# Rs485hub.net
KiCad netlist of a schematic drawn in EAGLE
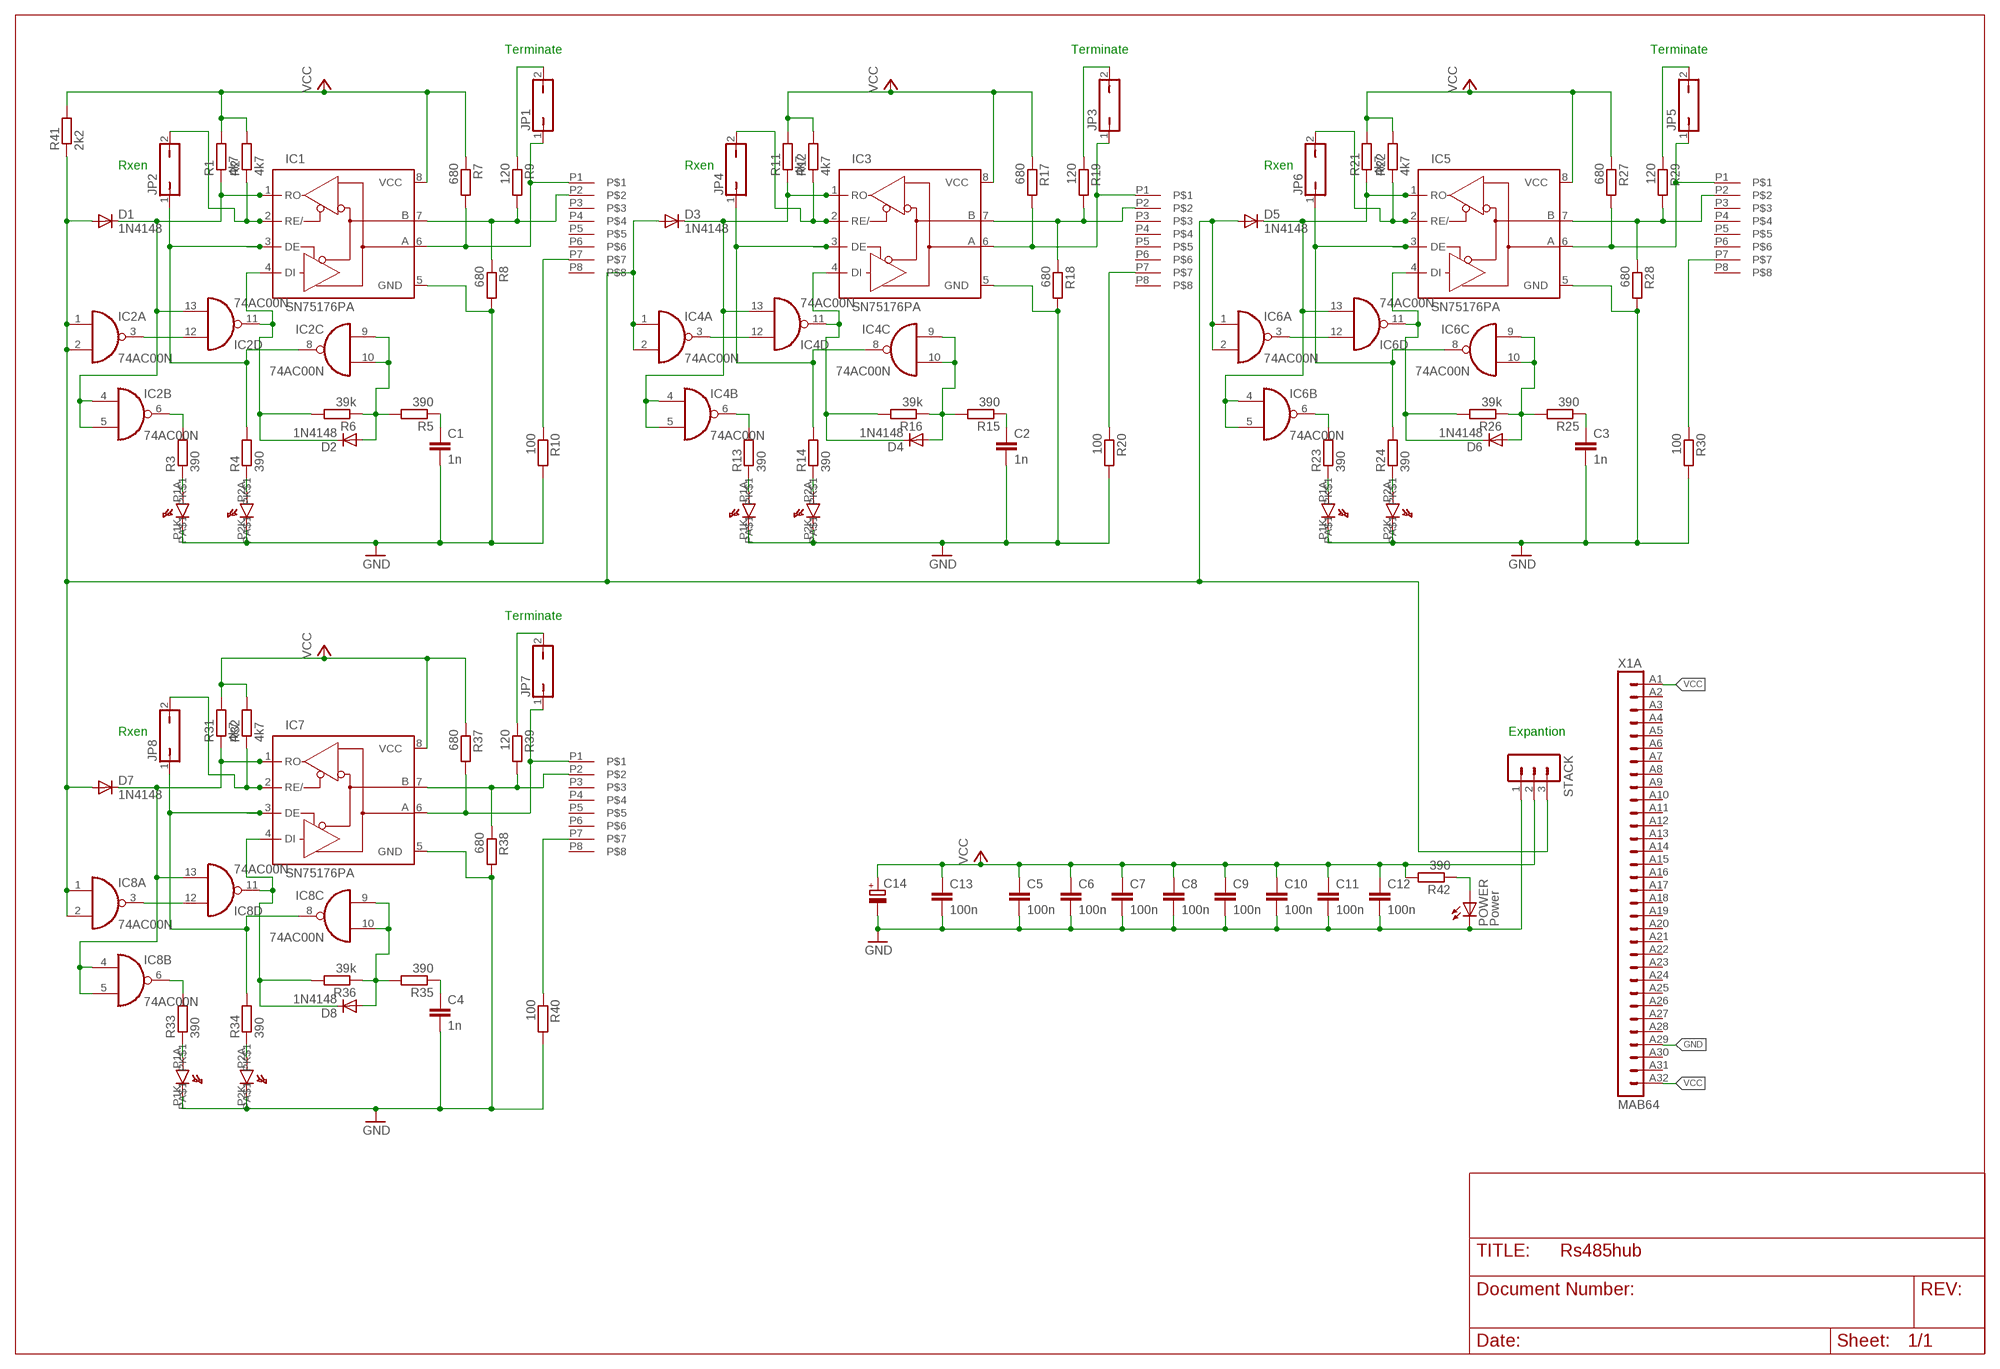
[diagram p0: schematic, sheet 1]

(export (version "E")
  (design (tool "Eeschema 10.0.6"))
  (components
    (comp (ref "C1")
      (value "1n")
      (footprint "eagle-import:C2.5-3")
      (libsource (lib "eagle-import") (part "C2,5-3"))
    )
    (comp (ref "C2")
      (value "1n")
      (footprint "eagle-import:C2.5-3")
      (libsource (lib "eagle-import") (part "C2,5-3"))
    )
    (comp (ref "C3")
      (value "1n")
      (footprint "eagle-import:C2.5-3")
      (libsource (lib "eagle-import") (part "C2,5-3"))
    )
    (comp (ref "C4")
      (value "1n")
      (footprint "eagle-import:C2.5-3")
      (libsource (lib "eagle-import") (part "C2,5-3"))
    )
    (comp (ref "C5")
      (value "100n")
      (footprint "eagle-import:C2.5-3")
      (libsource (lib "eagle-import") (part "C2,5-3"))
    )
    (comp (ref "C6")
      (value "100n")
      (footprint "eagle-import:C2.5-3")
      (libsource (lib "eagle-import") (part "C2,5-3"))
    )
    (comp (ref "C7")
      (value "100n")
      (footprint "eagle-import:C2.5-3")
      (libsource (lib "eagle-import") (part "C2,5-3"))
    )
    (comp (ref "C8")
      (value "100n")
      (footprint "eagle-import:C2.5-3")
      (libsource (lib "eagle-import") (part "C2,5-3"))
    )
    (comp (ref "C9")
      (value "100n")
      (footprint "eagle-import:C2.5-3")
      (libsource (lib "eagle-import") (part "C2,5-3"))
    )
    (comp (ref "C10")
      (value "100n")
      (footprint "eagle-import:C2.5-3")
      (libsource (lib "eagle-import") (part "C2,5-3"))
    )
    (comp (ref "C11")
      (value "100n")
      (footprint "eagle-import:C2.5-3")
      (libsource (lib "eagle-import") (part "C2,5-3"))
    )
    (comp (ref "C12")
      (value "100n")
      (footprint "eagle-import:C2.5-3")
      (libsource (lib "eagle-import") (part "C2,5-3"))
    )
    (comp (ref "C13")
      (value "100n")
      (footprint "eagle-import:C2.5-3")
      (libsource (lib "eagle-import") (part "C2,5-3"))
    )
    (comp (ref "C14")
      (value "CPOL-EUE5-8.5")
      (footprint "eagle-import:E5-8,5")
      (libsource (lib "eagle-import") (part "CPOL-EUE5-8.5"))
    )
    (comp (ref "D1")
      (value "1N4148")
      (footprint "eagle-import:DO35-10")
      (libsource (lib "eagle-import") (part "1N4148"))
    )
    (comp (ref "D2")
      (value "1N4148")
      (footprint "eagle-import:DO35-10")
      (libsource (lib "eagle-import") (part "1N4148"))
    )
    (comp (ref "D3")
      (value "1N4148")
      (footprint "eagle-import:DO35-10")
      (libsource (lib "eagle-import") (part "1N4148"))
    )
    (comp (ref "D4")
      (value "1N4148")
      (footprint "eagle-import:DO35-10")
      (libsource (lib "eagle-import") (part "1N4148"))
    )
    (comp (ref "D5")
      (value "1N4148")
      (footprint "eagle-import:DO35-10")
      (libsource (lib "eagle-import") (part "1N4148"))
    )
    (comp (ref "D6")
      (value "1N4148")
      (footprint "eagle-import:DO35-10")
      (libsource (lib "eagle-import") (part "1N4148"))
    )
    (comp (ref "D7")
      (value "1N4148")
      (footprint "eagle-import:DO35-10")
      (libsource (lib "eagle-import") (part "1N4148"))
    )
    (comp (ref "D8")
      (value "1N4148")
      (footprint "eagle-import:DO35-10")
      (libsource (lib "eagle-import") (part "1N4148"))
    )
    (comp (ref "IC1")
      (value "SN75176PA")
      (footprint "eagle-import:DIL08")
      (libsource (lib "eagle-import") (part "SN75176PA"))
    )
    (comp (ref "IC2")
      (value "74AC00N")
      (footprint "eagle-import:DIL14")
      (libsource (lib "eagle-import") (part "7400NAC"))
    )
    (comp (ref "IC3")
      (value "SN75176PA")
      (footprint "eagle-import:DIL08")
      (libsource (lib "eagle-import") (part "SN75176PA"))
    )
    (comp (ref "IC4")
      (value "74AC00N")
      (footprint "eagle-import:DIL14")
      (libsource (lib "eagle-import") (part "7400NAC"))
    )
    (comp (ref "IC5")
      (value "SN75176PA")
      (footprint "eagle-import:DIL08")
      (libsource (lib "eagle-import") (part "SN75176PA"))
    )
    (comp (ref "IC6")
      (value "74AC00N")
      (footprint "eagle-import:DIL14")
      (libsource (lib "eagle-import") (part "7400NAC"))
    )
    (comp (ref "IC7")
      (value "SN75176PA")
      (footprint "eagle-import:DIL08")
      (libsource (lib "eagle-import") (part "SN75176PA"))
    )
    (comp (ref "IC8")
      (value "74AC00N")
      (footprint "eagle-import:DIL14")
      (libsource (lib "eagle-import") (part "7400NAC"))
    )
    (comp (ref "JP1")
      (value "JP1Q")
      (footprint "eagle-import:JP1")
      (libsource (lib "eagle-import") (part "JP1Q"))
    )
    (comp (ref "JP2")
      (value "JP1Q")
      (footprint "eagle-import:JP1")
      (libsource (lib "eagle-import") (part "JP1Q"))
    )
    (comp (ref "JP3")
      (value "JP1Q")
      (footprint "eagle-import:JP1")
      (libsource (lib "eagle-import") (part "JP1Q"))
    )
    (comp (ref "JP4")
      (value "JP1Q")
      (footprint "eagle-import:JP1")
      (libsource (lib "eagle-import") (part "JP1Q"))
    )
    (comp (ref "JP5")
      (value "JP1Q")
      (footprint "eagle-import:JP1")
      (libsource (lib "eagle-import") (part "JP1Q"))
    )
    (comp (ref "JP6")
      (value "JP1Q")
      (footprint "eagle-import:JP1")
      (libsource (lib "eagle-import") (part "JP1Q"))
    )
    (comp (ref "JP7")
      (value "JP1Q")
      (footprint "eagle-import:JP1")
      (libsource (lib "eagle-import") (part "JP1Q"))
    )
    (comp (ref "JP8")
      (value "JP1Q")
      (footprint "eagle-import:JP1")
      (libsource (lib "eagle-import") (part "JP1Q"))
    )
    (comp (ref "POWER")
      (value "Power")
      (footprint "eagle-import:LED3MM")
      (libsource (lib "eagle-import") (part "LED3MM"))
    )
    (comp (ref "R1")
      (value "4k7")
      (footprint "eagle-import:0309_10")
      (libsource (lib "eagle-import") (part "R-EU_0309/10"))
    )
    (comp (ref "R2")
      (value "4k7")
      (footprint "eagle-import:0309_10")
      (libsource (lib "eagle-import") (part "R-EU_0309/10"))
    )
    (comp (ref "R3")
      (value "390")
      (footprint "eagle-import:0309_10")
      (libsource (lib "eagle-import") (part "R-EU_0309/10"))
    )
    (comp (ref "R4")
      (value "390")
      (footprint "eagle-import:0309_10")
      (libsource (lib "eagle-import") (part "R-EU_0309/10"))
    )
    (comp (ref "R5")
      (value "390")
      (footprint "eagle-import:0309_10")
      (libsource (lib "eagle-import") (part "R-EU_0309/10"))
    )
    (comp (ref "R6")
      (value "39k")
      (footprint "eagle-import:0309_10")
      (libsource (lib "eagle-import") (part "R-EU_0309/10"))
    )
    (comp (ref "R7")
      (value "680")
      (footprint "eagle-import:0309_10")
      (libsource (lib "eagle-import") (part "R-EU_0309/10"))
    )
    (comp (ref "R8")
      (value "680")
      (footprint "eagle-import:0309_10")
      (libsource (lib "eagle-import") (part "R-EU_0309/10"))
    )
    (comp (ref "R9")
      (value "120")
      (footprint "eagle-import:0309_10")
      (libsource (lib "eagle-import") (part "R-EU_0309/10"))
    )
    (comp (ref "R10")
      (value "100")
      (footprint "eagle-import:0309_10")
      (libsource (lib "eagle-import") (part "R-EU_0309/10"))
    )
    (comp (ref "R11")
      (value "4k7")
      (footprint "eagle-import:0309_10")
      (libsource (lib "eagle-import") (part "R-EU_0309/10"))
    )
    (comp (ref "R12")
      (value "4k7")
      (footprint "eagle-import:0309_10")
      (libsource (lib "eagle-import") (part "R-EU_0309/10"))
    )
    (comp (ref "R13")
      (value "390")
      (footprint "eagle-import:0309_10")
      (libsource (lib "eagle-import") (part "R-EU_0309/10"))
    )
    (comp (ref "R14")
      (value "390")
      (footprint "eagle-import:0309_10")
      (libsource (lib "eagle-import") (part "R-EU_0309/10"))
    )
    (comp (ref "R15")
      (value "390")
      (footprint "eagle-import:0309_10")
      (libsource (lib "eagle-import") (part "R-EU_0309/10"))
    )
    (comp (ref "R16")
      (value "39k")
      (footprint "eagle-import:0309_10")
      (libsource (lib "eagle-import") (part "R-EU_0309/10"))
    )
    (comp (ref "R17")
      (value "680")
      (footprint "eagle-import:0309_10")
      (libsource (lib "eagle-import") (part "R-EU_0309/10"))
    )
    (comp (ref "R18")
      (value "680")
      (footprint "eagle-import:0309_10")
      (libsource (lib "eagle-import") (part "R-EU_0309/10"))
    )
    (comp (ref "R19")
      (value "120")
      (footprint "eagle-import:0309_10")
      (libsource (lib "eagle-import") (part "R-EU_0309/10"))
    )
    (comp (ref "R20")
      (value "100")
      (footprint "eagle-import:0309_10")
      (libsource (lib "eagle-import") (part "R-EU_0309/10"))
    )
    (comp (ref "R21")
      (value "4k7")
      (footprint "eagle-import:0309_10")
      (libsource (lib "eagle-import") (part "R-EU_0309/10"))
    )
    (comp (ref "R22")
      (value "4k7")
      (footprint "eagle-import:0309_10")
      (libsource (lib "eagle-import") (part "R-EU_0309/10"))
    )
    (comp (ref "R23")
      (value "390")
      (footprint "eagle-import:0309_10")
      (libsource (lib "eagle-import") (part "R-EU_0309/10"))
    )
    (comp (ref "R24")
      (value "390")
      (footprint "eagle-import:0309_10")
      (libsource (lib "eagle-import") (part "R-EU_0309/10"))
    )
    (comp (ref "R25")
      (value "390")
      (footprint "eagle-import:0309_10")
      (libsource (lib "eagle-import") (part "R-EU_0309/10"))
    )
    (comp (ref "R26")
      (value "39k")
      (footprint "eagle-import:0309_10")
      (libsource (lib "eagle-import") (part "R-EU_0309/10"))
    )
    (comp (ref "R27")
      (value "680")
      (footprint "eagle-import:0309_10")
      (libsource (lib "eagle-import") (part "R-EU_0309/10"))
    )
    (comp (ref "R28")
      (value "680")
      (footprint "eagle-import:0309_10")
      (libsource (lib "eagle-import") (part "R-EU_0309/10"))
    )
    (comp (ref "R29")
      (value "120")
      (footprint "eagle-import:0309_10")
      (libsource (lib "eagle-import") (part "R-EU_0309/10"))
    )
    (comp (ref "R30")
      (value "100")
      (footprint "eagle-import:0309_10")
      (libsource (lib "eagle-import") (part "R-EU_0309/10"))
    )
    (comp (ref "R31")
      (value "4k7")
      (footprint "eagle-import:0309_10")
      (libsource (lib "eagle-import") (part "R-EU_0309/10"))
    )
    (comp (ref "R32")
      (value "4k7")
      (footprint "eagle-import:0309_10")
      (libsource (lib "eagle-import") (part "R-EU_0309/10"))
    )
    (comp (ref "R33")
      (value "390")
      (footprint "eagle-import:0309_10")
      (libsource (lib "eagle-import") (part "R-EU_0309/10"))
    )
    (comp (ref "R34")
      (value "390")
      (footprint "eagle-import:0309_10")
      (libsource (lib "eagle-import") (part "R-EU_0309/10"))
    )
    (comp (ref "R35")
      (value "390")
      (footprint "eagle-import:0309_10")
      (libsource (lib "eagle-import") (part "R-EU_0309/10"))
    )
    (comp (ref "R36")
      (value "39k")
      (footprint "eagle-import:0309_10")
      (libsource (lib "eagle-import") (part "R-EU_0309/10"))
    )
    (comp (ref "R37")
      (value "680")
      (footprint "eagle-import:0309_10")
      (libsource (lib "eagle-import") (part "R-EU_0309/10"))
    )
    (comp (ref "R38")
      (value "680")
      (footprint "eagle-import:0309_10")
      (libsource (lib "eagle-import") (part "R-EU_0309/10"))
    )
    (comp (ref "R39")
      (value "120")
      (footprint "eagle-import:0309_10")
      (libsource (lib "eagle-import") (part "R-EU_0309/10"))
    )
    (comp (ref "R40")
      (value "100")
      (footprint "eagle-import:0309_10")
      (libsource (lib "eagle-import") (part "R-EU_0309/10"))
    )
    (comp (ref "R41")
      (value "2k2")
      (footprint "eagle-import:0309_10")
      (libsource (lib "eagle-import") (part "R-EU_0309/10"))
    )
    (comp (ref "R42")
      (value "390")
      (footprint "eagle-import:0309_10")
      (libsource (lib "eagle-import") (part "R-EU_0309/10"))
    )
    (comp (ref "STACK")
      (value "MA03-1")
      (footprint "eagle-import:MA03-1")
      (libsource (lib "eagle-import") (part "MA03-1"))
    )
    (comp (ref "U$2")
      (value "RJHS508")
      (footprint "eagle-import:P-RJHS-538X")
      (libsource (lib "eagle-import") (part "RJHS508"))
    )
    (comp (ref "U$3")
      (value "RJHS508")
      (footprint "eagle-import:P-RJHS-538X")
      (libsource (lib "eagle-import") (part "RJHS508"))
    )
    (comp (ref "U$4")
      (value "RJHS508")
      (footprint "eagle-import:P-RJHS-538X")
      (libsource (lib "eagle-import") (part "RJHS508"))
    )
    (comp (ref "U$5")
      (value "RJHS508")
      (footprint "eagle-import:P-RJHS-538X")
      (libsource (lib "eagle-import") (part "RJHS508"))
    )
    (comp (ref "X1")
      (value "MAB64")
      (footprint "eagle-import:MAB64")
      (libsource (lib "eagle-import") (part "MAB64"))
    )
  )
  (nets
    (net (code "1") (name "GND") (class "Default")
      (node (ref "C1") (pin "2") (pinfunction "2_2") (pintype "passive"))
      (node (ref "C10") (pin "2") (pinfunction "2_2") (pintype "passive"))
      (node (ref "C11") (pin "2") (pinfunction "2_2") (pintype "passive"))
      (node (ref "C12") (pin "2") (pinfunction "2_2") (pintype "passive"))
      (node (ref "C13") (pin "2") (pinfunction "2_2") (pintype "passive"))
      (node (ref "C14") (pin "-") (pinfunction "-_-") (pintype "passive"))
      (node (ref "C2") (pin "2") (pinfunction "2_2") (pintype "passive"))
      (node (ref "C3") (pin "2") (pinfunction "2_2") (pintype "passive"))
      (node (ref "C4") (pin "2") (pinfunction "2_2") (pintype "passive"))
      (node (ref "C5") (pin "2") (pinfunction "2_2") (pintype "passive"))
      (node (ref "C6") (pin "2") (pinfunction "2_2") (pintype "passive"))
      (node (ref "C7") (pin "2") (pinfunction "2_2") (pintype "passive"))
      (node (ref "C8") (pin "2") (pinfunction "2_2") (pintype "passive"))
      (node (ref "C9") (pin "2") (pinfunction "2_2") (pintype "passive"))
      (node (ref "IC1") (pin "5") (pinfunction "GND_5") (pintype "power_in"))
      (node (ref "IC3") (pin "5") (pinfunction "GND_5") (pintype "power_in"))
      (node (ref "IC5") (pin "5") (pinfunction "GND_5") (pintype "power_in"))
      (node (ref "IC7") (pin "5") (pinfunction "GND_5") (pintype "power_in"))
      (node (ref "POWER") (pin "K") (pinfunction "C_K") (pintype "passive"))
      (node (ref "R10") (pin "2") (pinfunction "2_2") (pintype "passive"))
      (node (ref "R18") (pin "2") (pinfunction "2_2") (pintype "passive"))
      (node (ref "R20") (pin "2") (pinfunction "2_2") (pintype "passive"))
      (node (ref "R28") (pin "2") (pinfunction "2_2") (pintype "passive"))
      (node (ref "R30") (pin "2") (pinfunction "2_2") (pintype "passive"))
      (node (ref "R38") (pin "2") (pinfunction "2_2") (pintype "passive"))
      (node (ref "R40") (pin "2") (pinfunction "2_2") (pintype "passive"))
      (node (ref "R8") (pin "2") (pinfunction "2_2") (pintype "passive"))
      (node (ref "STACK") (pin "1") (pinfunction "1_1") (pintype "passive"))
      (node (ref "U$2") (pin "P1K") (pinfunction "PK$1_P1K") (pintype "bidirectional"))
      (node (ref "U$2") (pin "P2K") (pinfunction "PK$1_P2K") (pintype "bidirectional"))
      (node (ref "U$3") (pin "P1K") (pinfunction "PK$1_P1K") (pintype "bidirectional"))
      (node (ref "U$3") (pin "P2K") (pinfunction "PK$1_P2K") (pintype "bidirectional"))
      (node (ref "U$4") (pin "P1K") (pinfunction "PK$1_P1K") (pintype "bidirectional"))
      (node (ref "U$4") (pin "P2K") (pinfunction "PK$1_P2K") (pintype "bidirectional"))
      (node (ref "U$5") (pin "P1K") (pinfunction "PK$1_P1K") (pintype "bidirectional"))
      (node (ref "U$5") (pin "P2K") (pinfunction "PK$1_P2K") (pintype "bidirectional"))
      (node (ref "X1") (pin "A29") (pinfunction "29_A29") (pintype "passive"))
    )
    (net (code "2") (name "Net-(C1-Pad1)") (class "Default")
      (node (ref "C1") (pin "1") (pinfunction "1_1") (pintype "passive"))
      (node (ref "R5") (pin "1") (pinfunction "1_1") (pintype "passive"))
    )
    (net (code "3") (name "Net-(C2-Pad1)") (class "Default")
      (node (ref "C2") (pin "1") (pinfunction "1_1") (pintype "passive"))
      (node (ref "R15") (pin "1") (pinfunction "1_1") (pintype "passive"))
    )
    (net (code "4") (name "Net-(C3-Pad1)") (class "Default")
      (node (ref "C3") (pin "1") (pinfunction "1_1") (pintype "passive"))
      (node (ref "R25") (pin "1") (pinfunction "1_1") (pintype "passive"))
    )
    (net (code "5") (name "Net-(C4-Pad1)") (class "Default")
      (node (ref "C4") (pin "1") (pinfunction "1_1") (pintype "passive"))
      (node (ref "R35") (pin "1") (pinfunction "1_1") (pintype "passive"))
    )
    (net (code "6") (name "Net-(IC1-A)") (class "Default")
      (node (ref "IC1") (pin "6") (pinfunction "A_6") (pintype "passive"))
      (node (ref "JP1") (pin "1") (pinfunction "1_1") (pintype "passive"))
      (node (ref "R7") (pin "2") (pinfunction "2_2") (pintype "passive"))
      (node (ref "U$2") (pin "P1") (pinfunction "P$1_P1") (pintype "bidirectional"))
    )
    (net (code "7") (name "Net-(IC1-B)") (class "Default")
      (node (ref "IC1") (pin "7") (pinfunction "B_7") (pintype "passive"))
      (node (ref "R8") (pin "1") (pinfunction "1_1") (pintype "passive"))
      (node (ref "R9") (pin "2") (pinfunction "2_2") (pintype "passive"))
      (node (ref "U$2") (pin "P2") (pinfunction "P$2_P2") (pintype "bidirectional"))
    )
    (net (code "8") (name "Net-(IC1-DE)") (class "Default")
      (node (ref "IC1") (pin "3") (pinfunction "DE_3") (pintype "input"))
      (node (ref "IC2") (pin "8") (pinfunction "O_8") (pintype "output"))
      (node (ref "JP2") (pin "1") (pinfunction "1_1") (pintype "passive"))
      (node (ref "R4") (pin "2") (pinfunction "2_2") (pintype "passive"))
    )
    (net (code "9") (name "Net-(IC1-DI)") (class "Default")
      (node (ref "D2") (pin "C") (pinfunction "C_C") (pintype "passive"))
      (node (ref "IC1") (pin "4") (pinfunction "DI_4") (pintype "input"))
      (node (ref "IC2") (pin "11") (pinfunction "O_11") (pintype "output"))
      (node (ref "R6") (pin "2") (pinfunction "2_2") (pintype "passive"))
    )
    (net (code "10") (name "Net-(IC1-RE{slash})") (class "Default")
      (node (ref "IC1") (pin "2") (pinfunction "RE/_2") (pintype "input"))
      (node (ref "JP2") (pin "2") (pinfunction "2_2") (pintype "passive"))
      (node (ref "R2") (pin "1") (pinfunction "1_1") (pintype "passive"))
    )
    (net (code "11") (name "Net-(IC1-RO)") (class "Default")
      (node (ref "D1") (pin "C") (pinfunction "C_C") (pintype "passive"))
      (node (ref "IC1") (pin "1") (pinfunction "RO_1") (pintype "output"))
      (node (ref "IC2") (pin "13") (pinfunction "I1_13") (pintype "input"))
      (node (ref "IC2") (pin "4") (pinfunction "I0_4") (pintype "input"))
      (node (ref "IC2") (pin "5") (pinfunction "I1_5") (pintype "input"))
      (node (ref "R1") (pin "1") (pinfunction "1_1") (pintype "passive"))
    )
    (net (code "12") (name "Net-(IC2A-I0)") (class "Default")
      (node (ref "D1") (pin "A") (pinfunction "A_A") (pintype "passive"))
      (node (ref "D3") (pin "A") (pinfunction "A_A") (pintype "passive"))
      (node (ref "D5") (pin "A") (pinfunction "A_A") (pintype "passive"))
      (node (ref "D7") (pin "A") (pinfunction "A_A") (pintype "passive"))
      (node (ref "IC2") (pin "1") (pinfunction "I0_1") (pintype "input"))
      (node (ref "IC2") (pin "2") (pinfunction "I1_2") (pintype "input"))
      (node (ref "IC4") (pin "1") (pinfunction "I0_1") (pintype "input"))
      (node (ref "IC4") (pin "2") (pinfunction "I1_2") (pintype "input"))
      (node (ref "IC6") (pin "1") (pinfunction "I0_1") (pintype "input"))
      (node (ref "IC6") (pin "2") (pinfunction "I1_2") (pintype "input"))
      (node (ref "IC8") (pin "1") (pinfunction "I0_1") (pintype "input"))
      (node (ref "IC8") (pin "2") (pinfunction "I1_2") (pintype "input"))
      (node (ref "R41") (pin "1") (pinfunction "1_1") (pintype "passive"))
      (node (ref "STACK") (pin "3") (pinfunction "3_3") (pintype "passive"))
    )
    (net (code "13") (name "Net-(IC2A-O)") (class "Default")
      (node (ref "IC2") (pin "12") (pinfunction "I0_12") (pintype "input"))
      (node (ref "IC2") (pin "3") (pinfunction "O_3") (pintype "output"))
    )
    (net (code "14") (name "Net-(IC2B-O)") (class "Default")
      (node (ref "IC2") (pin "6") (pinfunction "O_6") (pintype "output"))
      (node (ref "R3") (pin "2") (pinfunction "2_2") (pintype "passive"))
    )
    (net (code "15") (name "Net-(IC2C-I0)") (class "Default")
      (node (ref "D2") (pin "A") (pinfunction "A_A") (pintype "passive"))
      (node (ref "IC2") (pin "10") (pinfunction "I1_10") (pintype "input"))
      (node (ref "IC2") (pin "9") (pinfunction "I0_9") (pintype "input"))
      (node (ref "R5") (pin "2") (pinfunction "2_2") (pintype "passive"))
      (node (ref "R6") (pin "1") (pinfunction "1_1") (pintype "passive"))
    )
    (net (code "16") (name "Net-(IC3-A)") (class "Default")
      (node (ref "IC3") (pin "6") (pinfunction "A_6") (pintype "passive"))
      (node (ref "JP3") (pin "1") (pinfunction "1_1") (pintype "passive"))
      (node (ref "R17") (pin "2") (pinfunction "2_2") (pintype "passive"))
      (node (ref "U$3") (pin "P1") (pinfunction "P$1_P1") (pintype "bidirectional"))
    )
    (net (code "17") (name "Net-(IC3-B)") (class "Default")
      (node (ref "IC3") (pin "7") (pinfunction "B_7") (pintype "passive"))
      (node (ref "R18") (pin "1") (pinfunction "1_1") (pintype "passive"))
      (node (ref "R19") (pin "2") (pinfunction "2_2") (pintype "passive"))
      (node (ref "U$3") (pin "P2") (pinfunction "P$2_P2") (pintype "bidirectional"))
    )
    (net (code "18") (name "Net-(IC3-DE)") (class "Default")
      (node (ref "IC3") (pin "3") (pinfunction "DE_3") (pintype "input"))
      (node (ref "IC4") (pin "8") (pinfunction "O_8") (pintype "output"))
      (node (ref "JP4") (pin "1") (pinfunction "1_1") (pintype "passive"))
      (node (ref "R14") (pin "2") (pinfunction "2_2") (pintype "passive"))
    )
    (net (code "19") (name "Net-(IC3-DI)") (class "Default")
      (node (ref "D4") (pin "C") (pinfunction "C_C") (pintype "passive"))
      (node (ref "IC3") (pin "4") (pinfunction "DI_4") (pintype "input"))
      (node (ref "IC4") (pin "11") (pinfunction "O_11") (pintype "output"))
      (node (ref "R16") (pin "2") (pinfunction "2_2") (pintype "passive"))
    )
    (net (code "20") (name "Net-(IC3-RE{slash})") (class "Default")
      (node (ref "IC3") (pin "2") (pinfunction "RE/_2") (pintype "input"))
      (node (ref "JP4") (pin "2") (pinfunction "2_2") (pintype "passive"))
      (node (ref "R12") (pin "1") (pinfunction "1_1") (pintype "passive"))
    )
    (net (code "21") (name "Net-(IC3-RO)") (class "Default")
      (node (ref "D3") (pin "C") (pinfunction "C_C") (pintype "passive"))
      (node (ref "IC3") (pin "1") (pinfunction "RO_1") (pintype "output"))
      (node (ref "IC4") (pin "13") (pinfunction "I1_13") (pintype "input"))
      (node (ref "IC4") (pin "4") (pinfunction "I0_4") (pintype "input"))
      (node (ref "IC4") (pin "5") (pinfunction "I1_5") (pintype "input"))
      (node (ref "R11") (pin "1") (pinfunction "1_1") (pintype "passive"))
    )
    (net (code "22") (name "Net-(IC4A-O)") (class "Default")
      (node (ref "IC4") (pin "12") (pinfunction "I0_12") (pintype "input"))
      (node (ref "IC4") (pin "3") (pinfunction "O_3") (pintype "output"))
    )
    (net (code "23") (name "Net-(IC4B-O)") (class "Default")
      (node (ref "IC4") (pin "6") (pinfunction "O_6") (pintype "output"))
      (node (ref "R13") (pin "2") (pinfunction "2_2") (pintype "passive"))
    )
    (net (code "24") (name "Net-(IC4C-I0)") (class "Default")
      (node (ref "D4") (pin "A") (pinfunction "A_A") (pintype "passive"))
      (node (ref "IC4") (pin "10") (pinfunction "I1_10") (pintype "input"))
      (node (ref "IC4") (pin "9") (pinfunction "I0_9") (pintype "input"))
      (node (ref "R15") (pin "2") (pinfunction "2_2") (pintype "passive"))
      (node (ref "R16") (pin "1") (pinfunction "1_1") (pintype "passive"))
    )
    (net (code "25") (name "Net-(IC5-A)") (class "Default")
      (node (ref "IC5") (pin "6") (pinfunction "A_6") (pintype "passive"))
      (node (ref "JP5") (pin "1") (pinfunction "1_1") (pintype "passive"))
      (node (ref "R27") (pin "2") (pinfunction "2_2") (pintype "passive"))
      (node (ref "U$4") (pin "P1") (pinfunction "P$1_P1") (pintype "bidirectional"))
    )
    (net (code "26") (name "Net-(IC5-B)") (class "Default")
      (node (ref "IC5") (pin "7") (pinfunction "B_7") (pintype "passive"))
      (node (ref "R28") (pin "1") (pinfunction "1_1") (pintype "passive"))
      (node (ref "R29") (pin "2") (pinfunction "2_2") (pintype "passive"))
      (node (ref "U$4") (pin "P2") (pinfunction "P$2_P2") (pintype "bidirectional"))
    )
    (net (code "27") (name "Net-(IC5-DE)") (class "Default")
      (node (ref "IC5") (pin "3") (pinfunction "DE_3") (pintype "input"))
      (node (ref "IC6") (pin "8") (pinfunction "O_8") (pintype "output"))
      (node (ref "JP6") (pin "1") (pinfunction "1_1") (pintype "passive"))
      (node (ref "R24") (pin "2") (pinfunction "2_2") (pintype "passive"))
    )
    (net (code "28") (name "Net-(IC5-DI)") (class "Default")
      (node (ref "D6") (pin "C") (pinfunction "C_C") (pintype "passive"))
      (node (ref "IC5") (pin "4") (pinfunction "DI_4") (pintype "input"))
      (node (ref "IC6") (pin "11") (pinfunction "O_11") (pintype "output"))
      (node (ref "R26") (pin "2") (pinfunction "2_2") (pintype "passive"))
    )
    (net (code "29") (name "Net-(IC5-RE{slash})") (class "Default")
      (node (ref "IC5") (pin "2") (pinfunction "RE/_2") (pintype "input"))
      (node (ref "JP6") (pin "2") (pinfunction "2_2") (pintype "passive"))
      (node (ref "R22") (pin "1") (pinfunction "1_1") (pintype "passive"))
    )
    (net (code "30") (name "Net-(IC5-RO)") (class "Default")
      (node (ref "D5") (pin "C") (pinfunction "C_C") (pintype "passive"))
      (node (ref "IC5") (pin "1") (pinfunction "RO_1") (pintype "output"))
      (node (ref "IC6") (pin "13") (pinfunction "I1_13") (pintype "input"))
      (node (ref "IC6") (pin "4") (pinfunction "I0_4") (pintype "input"))
      (node (ref "IC6") (pin "5") (pinfunction "I1_5") (pintype "input"))
      (node (ref "R21") (pin "1") (pinfunction "1_1") (pintype "passive"))
    )
    (net (code "31") (name "Net-(IC6A-O)") (class "Default")
      (node (ref "IC6") (pin "12") (pinfunction "I0_12") (pintype "input"))
      (node (ref "IC6") (pin "3") (pinfunction "O_3") (pintype "output"))
    )
    (net (code "32") (name "Net-(IC6B-O)") (class "Default")
      (node (ref "IC6") (pin "6") (pinfunction "O_6") (pintype "output"))
      (node (ref "R23") (pin "2") (pinfunction "2_2") (pintype "passive"))
    )
    (net (code "33") (name "Net-(IC6C-I0)") (class "Default")
      (node (ref "D6") (pin "A") (pinfunction "A_A") (pintype "passive"))
      (node (ref "IC6") (pin "10") (pinfunction "I1_10") (pintype "input"))
      (node (ref "IC6") (pin "9") (pinfunction "I0_9") (pintype "input"))
      (node (ref "R25") (pin "2") (pinfunction "2_2") (pintype "passive"))
      (node (ref "R26") (pin "1") (pinfunction "1_1") (pintype "passive"))
    )
    (net (code "34") (name "Net-(IC7-A)") (class "Default")
      (node (ref "IC7") (pin "6") (pinfunction "A_6") (pintype "passive"))
      (node (ref "JP7") (pin "1") (pinfunction "1_1") (pintype "passive"))
      (node (ref "R37") (pin "2") (pinfunction "2_2") (pintype "passive"))
      (node (ref "U$5") (pin "P1") (pinfunction "P$1_P1") (pintype "bidirectional"))
    )
    (net (code "35") (name "Net-(IC7-B)") (class "Default")
      (node (ref "IC7") (pin "7") (pinfunction "B_7") (pintype "passive"))
      (node (ref "R38") (pin "1") (pinfunction "1_1") (pintype "passive"))
      (node (ref "R39") (pin "2") (pinfunction "2_2") (pintype "passive"))
      (node (ref "U$5") (pin "P2") (pinfunction "P$2_P2") (pintype "bidirectional"))
    )
    (net (code "36") (name "Net-(IC7-DE)") (class "Default")
      (node (ref "IC7") (pin "3") (pinfunction "DE_3") (pintype "input"))
      (node (ref "IC8") (pin "8") (pinfunction "O_8") (pintype "output"))
      (node (ref "JP8") (pin "1") (pinfunction "1_1") (pintype "passive"))
      (node (ref "R34") (pin "2") (pinfunction "2_2") (pintype "passive"))
    )
    (net (code "37") (name "Net-(IC7-DI)") (class "Default")
      (node (ref "D8") (pin "C") (pinfunction "C_C") (pintype "passive"))
      (node (ref "IC7") (pin "4") (pinfunction "DI_4") (pintype "input"))
      (node (ref "IC8") (pin "11") (pinfunction "O_11") (pintype "output"))
      (node (ref "R36") (pin "2") (pinfunction "2_2") (pintype "passive"))
    )
    (net (code "38") (name "Net-(IC7-RE{slash})") (class "Default")
      (node (ref "IC7") (pin "2") (pinfunction "RE/_2") (pintype "input"))
      (node (ref "JP8") (pin "2") (pinfunction "2_2") (pintype "passive"))
      (node (ref "R32") (pin "1") (pinfunction "1_1") (pintype "passive"))
    )
    (net (code "39") (name "Net-(IC7-RO)") (class "Default")
      (node (ref "D7") (pin "C") (pinfunction "C_C") (pintype "passive"))
      (node (ref "IC7") (pin "1") (pinfunction "RO_1") (pintype "output"))
      (node (ref "IC8") (pin "13") (pinfunction "I1_13") (pintype "input"))
      (node (ref "IC8") (pin "4") (pinfunction "I0_4") (pintype "input"))
      (node (ref "IC8") (pin "5") (pinfunction "I1_5") (pintype "input"))
      (node (ref "R31") (pin "1") (pinfunction "1_1") (pintype "passive"))
    )
    (net (code "40") (name "Net-(IC8A-O)") (class "Default")
      (node (ref "IC8") (pin "12") (pinfunction "I0_12") (pintype "input"))
      (node (ref "IC8") (pin "3") (pinfunction "O_3") (pintype "output"))
    )
    (net (code "41") (name "Net-(IC8B-O)") (class "Default")
      (node (ref "IC8") (pin "6") (pinfunction "O_6") (pintype "output"))
      (node (ref "R33") (pin "2") (pinfunction "2_2") (pintype "passive"))
    )
    (net (code "42") (name "Net-(IC8C-I0)") (class "Default")
      (node (ref "D8") (pin "A") (pinfunction "A_A") (pintype "passive"))
      (node (ref "IC8") (pin "10") (pinfunction "I1_10") (pintype "input"))
      (node (ref "IC8") (pin "9") (pinfunction "I0_9") (pintype "input"))
      (node (ref "R35") (pin "2") (pinfunction "2_2") (pintype "passive"))
      (node (ref "R36") (pin "1") (pinfunction "1_1") (pintype "passive"))
    )
    (net (code "43") (name "Net-(JP1-Pad2)") (class "Default")
      (node (ref "JP1") (pin "2") (pinfunction "2_2") (pintype "passive"))
      (node (ref "R9") (pin "1") (pinfunction "1_1") (pintype "passive"))
    )
    (net (code "44") (name "Net-(JP3-Pad2)") (class "Default")
      (node (ref "JP3") (pin "2") (pinfunction "2_2") (pintype "passive"))
      (node (ref "R19") (pin "1") (pinfunction "1_1") (pintype "passive"))
    )
    (net (code "45") (name "Net-(JP5-Pad2)") (class "Default")
      (node (ref "JP5") (pin "2") (pinfunction "2_2") (pintype "passive"))
      (node (ref "R29") (pin "1") (pinfunction "1_1") (pintype "passive"))
    )
    (net (code "46") (name "Net-(JP7-Pad2)") (class "Default")
      (node (ref "JP7") (pin "2") (pinfunction "2_2") (pintype "passive"))
      (node (ref "R39") (pin "1") (pinfunction "1_1") (pintype "passive"))
    )
    (net (code "47") (name "Net-(POWER-PadA)") (class "Default")
      (node (ref "POWER") (pin "A") (pinfunction "A_A") (pintype "passive"))
      (node (ref "R42") (pin "1") (pinfunction "1_1") (pintype "passive"))
    )
    (net (code "48") (name "Net-(U$2A-P$7)") (class "Default")
      (node (ref "R10") (pin "1") (pinfunction "1_1") (pintype "passive"))
      (node (ref "U$2") (pin "P7") (pinfunction "P$7_P7") (pintype "bidirectional"))
    )
    (net (code "49") (name "Net-(U$2B-PA$1)") (class "Default")
      (node (ref "R3") (pin "1") (pinfunction "1_1") (pintype "passive"))
      (node (ref "U$2") (pin "P1A") (pinfunction "PA$1_P1A") (pintype "bidirectional"))
    )
    (net (code "50") (name "Net-(U$2C-PA$1)") (class "Default")
      (node (ref "R4") (pin "1") (pinfunction "1_1") (pintype "passive"))
      (node (ref "U$2") (pin "P2A") (pinfunction "PA$1_P2A") (pintype "bidirectional"))
    )
    (net (code "51") (name "Net-(U$3A-P$7)") (class "Default")
      (node (ref "R20") (pin "1") (pinfunction "1_1") (pintype "passive"))
      (node (ref "U$3") (pin "P7") (pinfunction "P$7_P7") (pintype "bidirectional"))
    )
    (net (code "52") (name "Net-(U$3B-PA$1)") (class "Default")
      (node (ref "R13") (pin "1") (pinfunction "1_1") (pintype "passive"))
      (node (ref "U$3") (pin "P1A") (pinfunction "PA$1_P1A") (pintype "bidirectional"))
    )
    (net (code "53") (name "Net-(U$3C-PA$1)") (class "Default")
      (node (ref "R14") (pin "1") (pinfunction "1_1") (pintype "passive"))
      (node (ref "U$3") (pin "P2A") (pinfunction "PA$1_P2A") (pintype "bidirectional"))
    )
    (net (code "54") (name "Net-(U$4A-P$7)") (class "Default")
      (node (ref "R30") (pin "1") (pinfunction "1_1") (pintype "passive"))
      (node (ref "U$4") (pin "P7") (pinfunction "P$7_P7") (pintype "bidirectional"))
    )
    (net (code "55") (name "Net-(U$4B-PA$1)") (class "Default")
      (node (ref "R23") (pin "1") (pinfunction "1_1") (pintype "passive"))
      (node (ref "U$4") (pin "P1A") (pinfunction "PA$1_P1A") (pintype "bidirectional"))
    )
    (net (code "56") (name "Net-(U$4C-PA$1)") (class "Default")
      (node (ref "R24") (pin "1") (pinfunction "1_1") (pintype "passive"))
      (node (ref "U$4") (pin "P2A") (pinfunction "PA$1_P2A") (pintype "bidirectional"))
    )
    (net (code "57") (name "Net-(U$5A-P$7)") (class "Default")
      (node (ref "R40") (pin "1") (pinfunction "1_1") (pintype "passive"))
      (node (ref "U$5") (pin "P7") (pinfunction "P$7_P7") (pintype "bidirectional"))
    )
    (net (code "58") (name "Net-(U$5B-PA$1)") (class "Default")
      (node (ref "R33") (pin "1") (pinfunction "1_1") (pintype "passive"))
      (node (ref "U$5") (pin "P1A") (pinfunction "PA$1_P1A") (pintype "bidirectional"))
    )
    (net (code "59") (name "Net-(U$5C-PA$1)") (class "Default")
      (node (ref "R34") (pin "1") (pinfunction "1_1") (pintype "passive"))
      (node (ref "U$5") (pin "P2A") (pinfunction "PA$1_P2A") (pintype "bidirectional"))
    )
    (net (code "60") (name "VCC") (class "Default")
      (node (ref "C10") (pin "1") (pinfunction "1_1") (pintype "passive"))
      (node (ref "C11") (pin "1") (pinfunction "1_1") (pintype "passive"))
      (node (ref "C12") (pin "1") (pinfunction "1_1") (pintype "passive"))
      (node (ref "C13") (pin "1") (pinfunction "1_1") (pintype "passive"))
      (node (ref "C14") (pin "+") (pinfunction "+_+") (pintype "passive"))
      (node (ref "C5") (pin "1") (pinfunction "1_1") (pintype "passive"))
      (node (ref "C6") (pin "1") (pinfunction "1_1") (pintype "passive"))
      (node (ref "C7") (pin "1") (pinfunction "1_1") (pintype "passive"))
      (node (ref "C8") (pin "1") (pinfunction "1_1") (pintype "passive"))
      (node (ref "C9") (pin "1") (pinfunction "1_1") (pintype "passive"))
      (node (ref "IC1") (pin "8") (pinfunction "VCC_8") (pintype "power_in"))
      (node (ref "IC3") (pin "8") (pinfunction "VCC_8") (pintype "power_in"))
      (node (ref "IC5") (pin "8") (pinfunction "VCC_8") (pintype "power_in"))
      (node (ref "IC7") (pin "8") (pinfunction "VCC_8") (pintype "power_in"))
      (node (ref "R1") (pin "2") (pinfunction "2_2") (pintype "passive"))
      (node (ref "R11") (pin "2") (pinfunction "2_2") (pintype "passive"))
      (node (ref "R12") (pin "2") (pinfunction "2_2") (pintype "passive"))
      (node (ref "R17") (pin "1") (pinfunction "1_1") (pintype "passive"))
      (node (ref "R2") (pin "2") (pinfunction "2_2") (pintype "passive"))
      (node (ref "R21") (pin "2") (pinfunction "2_2") (pintype "passive"))
      (node (ref "R22") (pin "2") (pinfunction "2_2") (pintype "passive"))
      (node (ref "R27") (pin "1") (pinfunction "1_1") (pintype "passive"))
      (node (ref "R31") (pin "2") (pinfunction "2_2") (pintype "passive"))
      (node (ref "R32") (pin "2") (pinfunction "2_2") (pintype "passive"))
      (node (ref "R37") (pin "1") (pinfunction "1_1") (pintype "passive"))
      (node (ref "R41") (pin "2") (pinfunction "2_2") (pintype "passive"))
      (node (ref "R42") (pin "2") (pinfunction "2_2") (pintype "passive"))
      (node (ref "R7") (pin "1") (pinfunction "1_1") (pintype "passive"))
      (node (ref "STACK") (pin "2") (pinfunction "2_2") (pintype "passive"))
      (node (ref "X1") (pin "A1") (pinfunction "1_A1") (pintype "passive"))
      (node (ref "X1") (pin "A32") (pinfunction "32_A32") (pintype "passive"))
    )
    (net (code "61") (name "unconnected-(U$2A-P$3-PadP3)") (class "Default")
      (node (ref "U$2") (pin "P3") (pinfunction "P$3_P3") (pintype "bidirectional"))
    )
    (net (code "62") (name "unconnected-(U$2A-P$4-PadP4)") (class "Default")
      (node (ref "U$2") (pin "P4") (pinfunction "P$4_P4") (pintype "bidirectional"))
    )
    (net (code "63") (name "unconnected-(U$2A-P$5-PadP5)") (class "Default")
      (node (ref "U$2") (pin "P5") (pinfunction "P$5_P5") (pintype "bidirectional"))
    )
    (net (code "64") (name "unconnected-(U$2A-P$6-PadP6)") (class "Default")
      (node (ref "U$2") (pin "P6") (pinfunction "P$6_P6") (pintype "bidirectional"))
    )
    (net (code "65") (name "unconnected-(U$2A-P$8-PadP8)") (class "Default")
      (node (ref "U$2") (pin "P8") (pinfunction "P$8_P8") (pintype "bidirectional"))
    )
    (net (code "66") (name "unconnected-(U$3A-P$3-PadP3)") (class "Default")
      (node (ref "U$3") (pin "P3") (pinfunction "P$3_P3") (pintype "bidirectional"))
    )
    (net (code "67") (name "unconnected-(U$3A-P$4-PadP4)") (class "Default")
      (node (ref "U$3") (pin "P4") (pinfunction "P$4_P4") (pintype "bidirectional"))
    )
    (net (code "68") (name "unconnected-(U$3A-P$5-PadP5)") (class "Default")
      (node (ref "U$3") (pin "P5") (pinfunction "P$5_P5") (pintype "bidirectional"))
    )
    (net (code "69") (name "unconnected-(U$3A-P$6-PadP6)") (class "Default")
      (node (ref "U$3") (pin "P6") (pinfunction "P$6_P6") (pintype "bidirectional"))
    )
    (net (code "70") (name "unconnected-(U$3A-P$8-PadP8)") (class "Default")
      (node (ref "U$3") (pin "P8") (pinfunction "P$8_P8") (pintype "bidirectional"))
    )
    (net (code "71") (name "unconnected-(U$4A-P$3-PadP3)") (class "Default")
      (node (ref "U$4") (pin "P3") (pinfunction "P$3_P3") (pintype "bidirectional"))
    )
    (net (code "72") (name "unconnected-(U$4A-P$4-PadP4)") (class "Default")
      (node (ref "U$4") (pin "P4") (pinfunction "P$4_P4") (pintype "bidirectional"))
    )
    (net (code "73") (name "unconnected-(U$4A-P$5-PadP5)") (class "Default")
      (node (ref "U$4") (pin "P5") (pinfunction "P$5_P5") (pintype "bidirectional"))
    )
    (net (code "74") (name "unconnected-(U$4A-P$6-PadP6)") (class "Default")
      (node (ref "U$4") (pin "P6") (pinfunction "P$6_P6") (pintype "bidirectional"))
    )
    (net (code "75") (name "unconnected-(U$4A-P$8-PadP8)") (class "Default")
      (node (ref "U$4") (pin "P8") (pinfunction "P$8_P8") (pintype "bidirectional"))
    )
    (net (code "76") (name "unconnected-(U$5A-P$3-PadP3)") (class "Default")
      (node (ref "U$5") (pin "P3") (pinfunction "P$3_P3") (pintype "bidirectional"))
    )
    (net (code "77") (name "unconnected-(U$5A-P$4-PadP4)") (class "Default")
      (node (ref "U$5") (pin "P4") (pinfunction "P$4_P4") (pintype "bidirectional"))
    )
    (net (code "78") (name "unconnected-(U$5A-P$5-PadP5)") (class "Default")
      (node (ref "U$5") (pin "P5") (pinfunction "P$5_P5") (pintype "bidirectional"))
    )
    (net (code "79") (name "unconnected-(U$5A-P$6-PadP6)") (class "Default")
      (node (ref "U$5") (pin "P6") (pinfunction "P$6_P6") (pintype "bidirectional"))
    )
    (net (code "80") (name "unconnected-(U$5A-P$8-PadP8)") (class "Default")
      (node (ref "U$5") (pin "P8") (pinfunction "P$8_P8") (pintype "bidirectional"))
    )
    (net (code "81") (name "unconnected-(X1A-2-PadA2)") (class "Default")
      (node (ref "X1") (pin "A2") (pinfunction "2_A2") (pintype "passive"))
    )
    (net (code "82") (name "unconnected-(X1A-3-PadA3)") (class "Default")
      (node (ref "X1") (pin "A3") (pinfunction "3_A3") (pintype "passive"))
    )
    (net (code "83") (name "unconnected-(X1A-4-PadA4)") (class "Default")
      (node (ref "X1") (pin "A4") (pinfunction "4_A4") (pintype "passive"))
    )
    (net (code "84") (name "unconnected-(X1A-5-PadA5)") (class "Default")
      (node (ref "X1") (pin "A5") (pinfunction "5_A5") (pintype "passive"))
    )
    (net (code "85") (name "unconnected-(X1A-6-PadA6)") (class "Default")
      (node (ref "X1") (pin "A6") (pinfunction "6_A6") (pintype "passive"))
    )
    (net (code "86") (name "unconnected-(X1A-7-PadA7)") (class "Default")
      (node (ref "X1") (pin "A7") (pinfunction "7_A7") (pintype "passive"))
    )
    (net (code "87") (name "unconnected-(X1A-8-PadA8)") (class "Default")
      (node (ref "X1") (pin "A8") (pinfunction "8_A8") (pintype "passive"))
    )
    (net (code "88") (name "unconnected-(X1A-9-PadA9)") (class "Default")
      (node (ref "X1") (pin "A9") (pinfunction "9_A9") (pintype "passive"))
    )
    (net (code "89") (name "unconnected-(X1A-10-PadA10)") (class "Default")
      (node (ref "X1") (pin "A10") (pinfunction "10_A10") (pintype "passive"))
    )
    (net (code "90") (name "unconnected-(X1A-11-PadA11)") (class "Default")
      (node (ref "X1") (pin "A11") (pinfunction "11_A11") (pintype "passive"))
    )
    (net (code "91") (name "unconnected-(X1A-12-PadA12)") (class "Default")
      (node (ref "X1") (pin "A12") (pinfunction "12_A12") (pintype "passive"))
    )
    (net (code "92") (name "unconnected-(X1A-13-PadA13)") (class "Default")
      (node (ref "X1") (pin "A13") (pinfunction "13_A13") (pintype "passive"))
    )
    (net (code "93") (name "unconnected-(X1A-14-PadA14)") (class "Default")
      (node (ref "X1") (pin "A14") (pinfunction "14_A14") (pintype "passive"))
    )
    (net (code "94") (name "unconnected-(X1A-15-PadA15)") (class "Default")
      (node (ref "X1") (pin "A15") (pinfunction "15_A15") (pintype "passive"))
    )
    (net (code "95") (name "unconnected-(X1A-16-PadA16)") (class "Default")
      (node (ref "X1") (pin "A16") (pinfunction "16_A16") (pintype "passive"))
    )
    (net (code "96") (name "unconnected-(X1A-17-PadA17)") (class "Default")
      (node (ref "X1") (pin "A17") (pinfunction "17_A17") (pintype "passive"))
    )
    (net (code "97") (name "unconnected-(X1A-18-PadA18)") (class "Default")
      (node (ref "X1") (pin "A18") (pinfunction "18_A18") (pintype "passive"))
    )
    (net (code "98") (name "unconnected-(X1A-19-PadA19)") (class "Default")
      (node (ref "X1") (pin "A19") (pinfunction "19_A19") (pintype "passive"))
    )
    (net (code "99") (name "unconnected-(X1A-20-PadA20)") (class "Default")
      (node (ref "X1") (pin "A20") (pinfunction "20_A20") (pintype "passive"))
    )
    (net (code "100") (name "unconnected-(X1A-21-PadA21)") (class "Default")
      (node (ref "X1") (pin "A21") (pinfunction "21_A21") (pintype "passive"))
    )
    (net (code "101") (name "unconnected-(X1A-22-PadA22)") (class "Default")
      (node (ref "X1") (pin "A22") (pinfunction "22_A22") (pintype "passive"))
    )
    (net (code "102") (name "unconnected-(X1A-23-PadA23)") (class "Default")
      (node (ref "X1") (pin "A23") (pinfunction "23_A23") (pintype "passive"))
    )
    (net (code "103") (name "unconnected-(X1A-24-PadA24)") (class "Default")
      (node (ref "X1") (pin "A24") (pinfunction "24_A24") (pintype "passive"))
    )
    (net (code "104") (name "unconnected-(X1A-25-PadA25)") (class "Default")
      (node (ref "X1") (pin "A25") (pinfunction "25_A25") (pintype "passive"))
    )
    (net (code "105") (name "unconnected-(X1A-26-PadA26)") (class "Default")
      (node (ref "X1") (pin "A26") (pinfunction "26_A26") (pintype "passive"))
    )
    (net (code "106") (name "unconnected-(X1A-27-PadA27)") (class "Default")
      (node (ref "X1") (pin "A27") (pinfunction "27_A27") (pintype "passive"))
    )
    (net (code "107") (name "unconnected-(X1A-28-PadA28)") (class "Default")
      (node (ref "X1") (pin "A28") (pinfunction "28_A28") (pintype "passive"))
    )
    (net (code "108") (name "unconnected-(X1A-30-PadA30)") (class "Default")
      (node (ref "X1") (pin "A30") (pinfunction "30_A30") (pintype "passive"))
    )
    (net (code "109") (name "unconnected-(X1A-31-PadA31)") (class "Default")
      (node (ref "X1") (pin "A31") (pinfunction "31_A31") (pintype "passive"))
    )
  )
)
